# 01_V5_SYS.net
KiCad netlist of a schematic drawn in Altium Designer
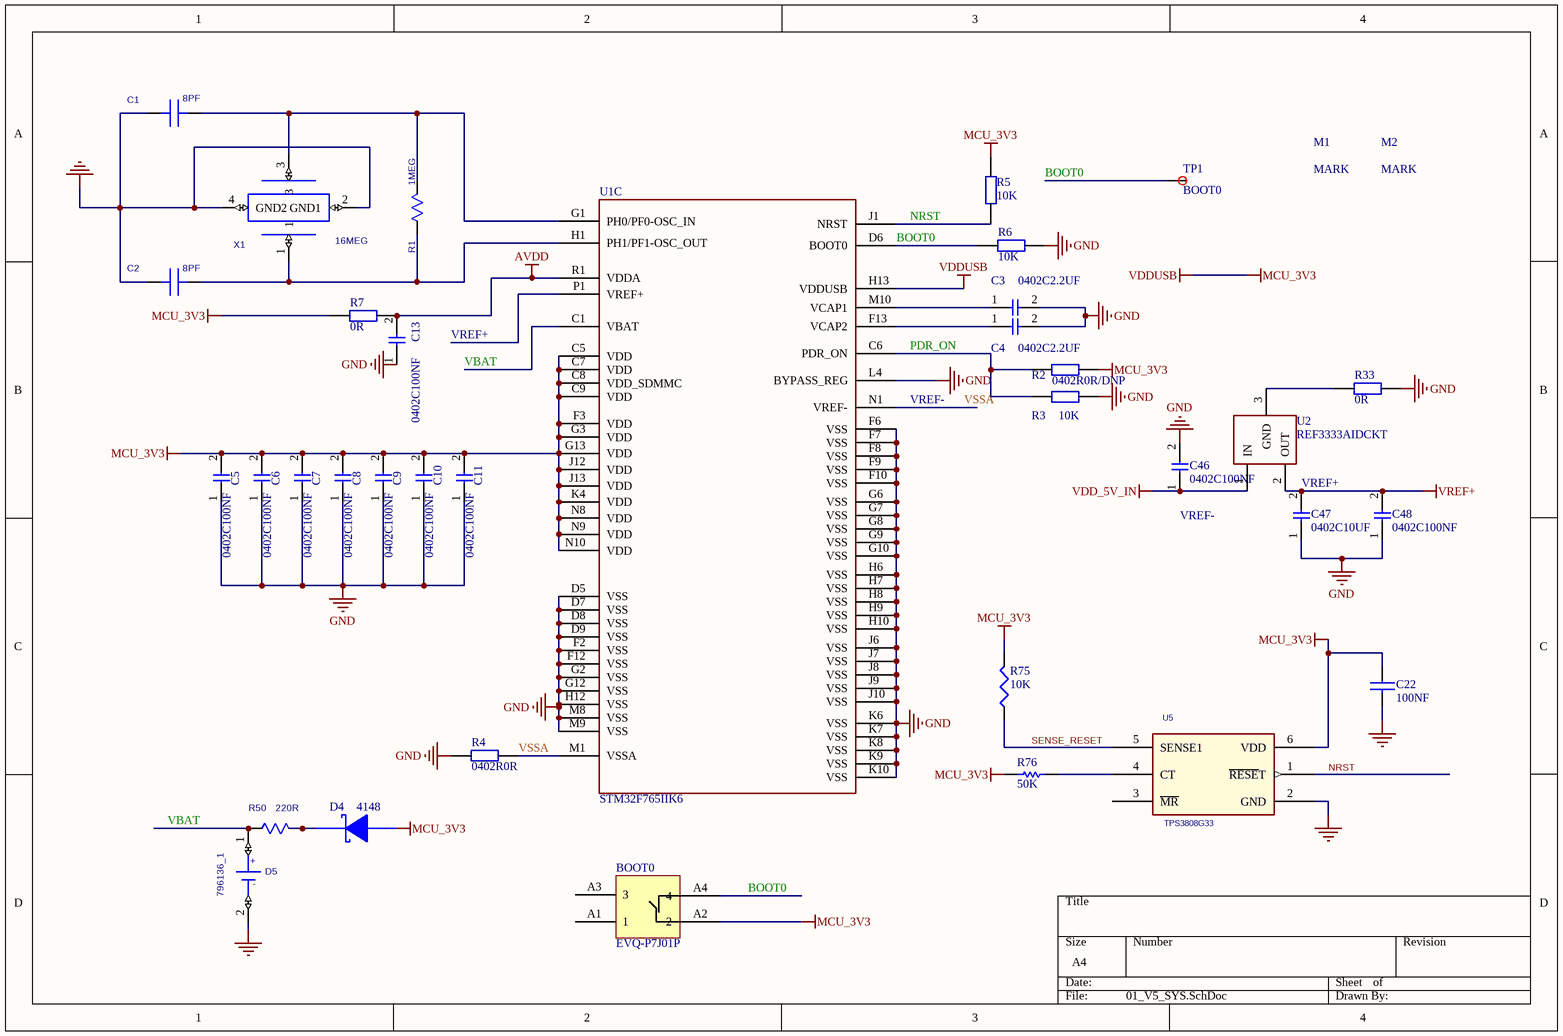
[diagram p0: 01_V5_SYS.SchDoc]

(export (version "E")
  (design (tool "Eeschema 10.0.6"))
  (components
    (comp (ref "BOOT0")
      (value "EVQ-P7J01P")
      (footprint "EVQ-P7J01P")
      (libsource (lib "hack") (part "EVQ-P7J01P"))
    )
    (comp (ref "C1") (value "8PF") (footprint "SC0402") (libsource (lib "*") (part "C")))
    (comp (ref "C2") (value "8PF") (footprint "SC0402") (libsource (lib "*") (part "C")))
    (comp (ref "C3") (value "0402C2.2UF") (footprint "0402C") (libsource (lib "CUAV") (part "0402C2.2UF")))
    (comp (ref "C4") (value "0402C2.2UF") (footprint "0402C") (libsource (lib "CUAV") (part "0402C2.2UF")))
    (comp (ref "C5")
      (value "0402C100NF")
      (footprint "0402C")
      (description "50V 5%")
      (libsource (lib "CUAV") (part "0402C100NF"))
    )
    (comp (ref "C6")
      (value "0402C100NF")
      (footprint "0402C")
      (description "50V 5%")
      (libsource (lib "CUAV") (part "0402C100NF"))
    )
    (comp (ref "C7")
      (value "0402C100NF")
      (footprint "0402C")
      (description "50V 5%")
      (libsource (lib "CUAV") (part "0402C100NF"))
    )
    (comp (ref "C8")
      (value "0402C100NF")
      (footprint "0402C")
      (description "50V 5%")
      (libsource (lib "CUAV") (part "0402C100NF"))
    )
    (comp (ref "C9")
      (value "0402C100NF")
      (footprint "0402C")
      (description "50V 5%")
      (libsource (lib "CUAV") (part "0402C100NF"))
    )
    (comp (ref "C10")
      (value "0402C100NF")
      (footprint "0402C")
      (description "50V 5%")
      (libsource (lib "CUAV") (part "0402C100NF"))
    )
    (comp (ref "C11")
      (value "0402C100NF")
      (footprint "0402C")
      (description "50V 5%")
      (libsource (lib "CUAV") (part "0402C100NF"))
    )
    (comp (ref "C13")
      (value "0402C100NF")
      (footprint "0402C")
      (description "50V 5%")
      (libsource (lib "CUAV") (part "0402C100NF"))
    )
    (comp (ref "C22")
      (value "100NF")
      (footprint "0402cap")
      (libsource (lib "Integrated_Library_RF_FEB_2012") (part "C1005X5R1H104K"))
    )
    (comp (ref "C46") (value "0402C100NF") (footprint "0402C") (libsource (lib "CUAV") (part "0402C2.2UF")))
    (comp (ref "C47") (value "0402C10UF") (footprint "0402C") (libsource (lib "CUAV") (part "0402C2.2UF")))
    (comp (ref "C48") (value "0402C100NF") (footprint "0402C") (libsource (lib "CUAV") (part "0402C2.2UF")))
    (comp (ref "D4")
      (value "4148")
      (footprint "SOD323")
      (description "STPS20M100SG-TR")
      (libsource (lib "TI WEBENCH") (part "D1"))
    )
    (comp (ref "D5")
      (value "PWR1-2")
      (footprint "PAS414R-S-VE5R")
      (fields (field (name "DEVICE") "796136_1"))
      (libsource (lib "*") (part "PWR1-2_1"))
    )
    (comp (ref "M1") (value "MARK") (footprint "MARK") (libsource (lib "CUAV") (part "MARK")))
    (comp (ref "M2") (value "MARK") (footprint "MARK") (libsource (lib "CUAV") (part "MARK")))
    (comp (ref "R1") (value "1MEG") (footprint "SR0402") (libsource (lib "*") (part "R")))
    (comp (ref "R2")
      (value "0402R0R/DNP")
      (footprint "0402R")
      (description "0402R0R 1%")
      (libsource (lib "CUAV") (part "0402R0R"))
    )
    (comp (ref "R3")
      (value "10K")
      (footprint "0402R")
      (description "0402R0R 1%")
      (libsource (lib "CUAV") (part "0402R0R"))
    )
    (comp (ref "R4")
      (value "0402R0R")
      (footprint "0402R")
      (description "0402R0R 1%")
      (libsource (lib "CUAV") (part "0402R0R"))
    )
    (comp (ref "R5")
      (value "10K")
      (footprint "0402R")
      (description "0402R0R 1%")
      (libsource (lib "") (part "0402R0R_1"))
    )
    (comp (ref "R6")
      (value "10K")
      (footprint "0402R")
      (description "0402R0R 1%")
      (libsource (lib "") (part "0402R0R_2"))
    )
    (comp (ref "R7")
      (value "0R")
      (footprint "0402R")
      (description "0402R0R 1%")
      (libsource (lib "") (part "0402R0R_2"))
    )
    (comp (ref "R33")
      (value "0R")
      (footprint "0402R")
      (description "0402R0R 1%")
      (libsource (lib "") (part "0402R0R_2"))
    )
    (comp (ref "R50") (value "220R") (footprint "0402r") (libsource (lib "*") (part "R")))
    (comp (ref "R75")
      (value "10K")
      (footprint "R0402")
      (libsource (lib "Integrated_Library_RF_FEB_2012") (part "RMCF0402FT4K99"))
    )
    (comp (ref "R76")
      (value "50K")
      (footprint "0402R")
      (description "Semiconductor Resistor")
      (libsource (lib "Miscellaneous Devices") (part "Res Semi"))
    )
    (comp (ref "TP1")
      (value "BOOT0")
      (footprint "TP0.75")
      (description "TP_0.75MM")
      (libsource (lib "CUAV") (part "TP_0.75"))
    )
    (comp (ref "U1")
      (value "STM32F765IIK6")
      (footprint "UFBGA176")
      (libsource (lib "CUAV") (part "STM32F765IIK6"))
    )
    (comp (ref "U2")
      (value "REF3333AIDCKT")
      (footprint "SC70")
      (libsource (lib "CUAV") (part "REF3333AIDCKT"))
    )
    (comp (ref "U5")
      (value "TPS3808G33")
      (footprint "SOT-23-6")
      (description "IC VOLT SUPERVISOR 0.9V SOT23-6")
      (fields (field (name "PART #") "102020-0009R") (field (name "MANUFACTURER") "Texas Instruments"))
      (libsource (lib "Integrated_Library_RF_FEB_2012") (part "TPS3808G09DBVR"))
    )
    (comp (ref "X1") (value "16MEG") (footprint "3225") (libsource (lib "*") (part "X_B")))
  )
  (nets
    (net (code "1") (name "/BOOT0") (class "Default")
      (node (ref "BOOT0") (pin "A4") (pinfunction "4_A4") (pintype "passive"))
      (node (ref "R6") (pin "2") (pintype "passive"))
      (node (ref "TP1") (pin "0") (pintype "passive"))
      (node (ref "U1") (pin "D6") (pinfunction "BOOT0_D6") (pintype "passive"))
    )
    (net (code "2") (name "/NRST") (class "Default")
      (node (ref "R5") (pin "1") (pintype "passive"))
      (node (ref "U1") (pin "J1") (pinfunction "NRST_J1") (pintype "passive"))
      (node (ref "U5") (pin "1") (pinfunction "~{RESE}T_1") (pintype "output"))
    )
    (net (code "3") (name "/PDR_ON") (class "Default")
      (node (ref "R2") (pin "1") (pintype "passive"))
      (node (ref "R3") (pin "1") (pintype "passive"))
      (node (ref "U1") (pin "C6") (pinfunction "PDR_ON_C6") (pintype "passive"))
    )
    (net (code "4") (name "/SENSE_RESET") (class "Default")
      (node (ref "R75") (pin "1") (pinfunction "1_1") (pintype "passive"))
      (node (ref "U5") (pin "5") (pinfunction "SENSE1_5") (pintype "passive"))
    )
    (net (code "5") (name "/VBAT") (class "Default")
      (node (ref "D5") (pin "1") (pinfunction "+_1") (pintype "bidirectional"))
      (node (ref "R50") (pin "1") (pinfunction "A_1") (pintype "bidirectional"))
      (node (ref "U1") (pin "C1") (pinfunction "VBAT_C1") (pintype "passive"))
    )
    (net (code "6") (name "/VREF-") (class "Default")
      (node (ref "R4") (pin "2") (pintype "passive"))
      (node (ref "U1") (pin "M1") (pinfunction "VSSA_M1") (pintype "passive"))
      (node (ref "U1") (pin "N1") (pinfunction "VREF-_N1") (pintype "passive"))
    )
    (net (code "7") (name "AVDD") (class "Default")
      (node (ref "C13") (pin "2") (pintype "passive"))
      (node (ref "R7") (pin "1") (pintype "passive"))
      (node (ref "U1") (pin "R1") (pinfunction "VDDA_R1") (pintype "passive"))
    )
    (net (code "8") (name "GND") (class "Default")
      (node (ref "C1") (pin "1") (pinfunction "A_1") (pintype "bidirectional"))
      (node (ref "C10") (pin "1") (pintype "passive"))
      (node (ref "C11") (pin "1") (pintype "passive"))
      (node (ref "C13") (pin "1") (pintype "passive"))
      (node (ref "C2") (pin "1") (pinfunction "A_1") (pintype "bidirectional"))
      (node (ref "C22") (pin "2") (pinfunction "2_2") (pintype "passive"))
      (node (ref "C3") (pin "2") (pintype "passive"))
      (node (ref "C4") (pin "2") (pintype "passive"))
      (node (ref "C46") (pin "2") (pintype "passive"))
      (node (ref "C47") (pin "1") (pintype "passive"))
      (node (ref "C48") (pin "1") (pintype "passive"))
      (node (ref "C5") (pin "1") (pintype "passive"))
      (node (ref "C6") (pin "1") (pintype "passive"))
      (node (ref "C7") (pin "1") (pintype "passive"))
      (node (ref "C8") (pin "1") (pintype "passive"))
      (node (ref "C9") (pin "1") (pintype "passive"))
      (node (ref "D5") (pin "2") (pinfunction "-_2") (pintype "bidirectional"))
      (node (ref "R3") (pin "2") (pintype "passive"))
      (node (ref "R33") (pin "1") (pintype "passive"))
      (node (ref "R4") (pin "1") (pintype "passive"))
      (node (ref "R6") (pin "1") (pintype "passive"))
      (node (ref "U1") (pin "D5") (pinfunction "VSS_D5") (pintype "passive"))
      (node (ref "U1") (pin "D7") (pinfunction "VSS_D7") (pintype "passive"))
      (node (ref "U1") (pin "D8") (pinfunction "VSS_D8") (pintype "passive"))
      (node (ref "U1") (pin "D9") (pinfunction "VSS_D9") (pintype "passive"))
      (node (ref "U1") (pin "F10") (pinfunction "VSS_F10") (pintype "passive"))
      (node (ref "U1") (pin "F12") (pinfunction "VSS_F12") (pintype "passive"))
      (node (ref "U1") (pin "F2") (pinfunction "VSS_F2") (pintype "passive"))
      (node (ref "U1") (pin "F6") (pinfunction "VSS_F6") (pintype "passive"))
      (node (ref "U1") (pin "F7") (pinfunction "VSS_F7") (pintype "passive"))
      (node (ref "U1") (pin "F8") (pinfunction "VSS_F8") (pintype "passive"))
      (node (ref "U1") (pin "F9") (pinfunction "VSS_F9") (pintype "passive"))
      (node (ref "U1") (pin "G10") (pinfunction "VSS_G10") (pintype "passive"))
      (node (ref "U1") (pin "G12") (pinfunction "VSS_G12") (pintype "passive"))
      (node (ref "U1") (pin "G2") (pinfunction "VSS_G2") (pintype "passive"))
      (node (ref "U1") (pin "G6") (pinfunction "VSS_G6") (pintype "passive"))
      (node (ref "U1") (pin "G7") (pinfunction "VSS_G7") (pintype "passive"))
      (node (ref "U1") (pin "G8") (pinfunction "VSS_G8") (pintype "passive"))
      (node (ref "U1") (pin "G9") (pinfunction "VSS_G9") (pintype "passive"))
      (node (ref "U1") (pin "H10") (pinfunction "VSS_H10") (pintype "passive"))
      (node (ref "U1") (pin "H12") (pinfunction "VSS_H12") (pintype "passive"))
      (node (ref "U1") (pin "H6") (pinfunction "VSS_H6") (pintype "passive"))
      (node (ref "U1") (pin "H7") (pinfunction "VSS_H7") (pintype "passive"))
      (node (ref "U1") (pin "H8") (pinfunction "VSS_H8") (pintype "passive"))
      (node (ref "U1") (pin "H9") (pinfunction "VSS_H9") (pintype "passive"))
      (node (ref "U1") (pin "J10") (pinfunction "VSS_J10") (pintype "passive"))
      (node (ref "U1") (pin "J6") (pinfunction "VSS_J6") (pintype "passive"))
      (node (ref "U1") (pin "J7") (pinfunction "VSS_J7") (pintype "passive"))
      (node (ref "U1") (pin "J8") (pinfunction "VSS_J8") (pintype "passive"))
      (node (ref "U1") (pin "J9") (pinfunction "VSS_J9") (pintype "passive"))
      (node (ref "U1") (pin "K10") (pinfunction "VSS_K10") (pintype "passive"))
      (node (ref "U1") (pin "K6") (pinfunction "VSS_K6") (pintype "passive"))
      (node (ref "U1") (pin "K7") (pinfunction "VSS_K7") (pintype "passive"))
      (node (ref "U1") (pin "K8") (pinfunction "VSS_K8") (pintype "passive"))
      (node (ref "U1") (pin "K9") (pinfunction "VSS_K9") (pintype "passive"))
      (node (ref "U1") (pin "L4") (pinfunction "BYPASS_REG_L4") (pintype "passive"))
      (node (ref "U1") (pin "M8") (pinfunction "VSS_M8") (pintype "passive"))
      (node (ref "U1") (pin "M9") (pinfunction "VSS_M9") (pintype "passive"))
      (node (ref "U5") (pin "2") (pinfunction "GND_2") (pintype "passive"))
      (node (ref "X1") (pin "2") (pinfunction "GND1_2") (pintype "bidirectional"))
      (node (ref "X1") (pin "4") (pinfunction "GND2_4") (pintype "bidirectional"))
    )
    (net (code "9") (name "MCU_3V3") (class "Default")
      (node (ref "BOOT0") (pin "A2") (pinfunction "2_A2") (pintype "passive"))
      (node (ref "C10") (pin "2") (pintype "passive"))
      (node (ref "C11") (pin "2") (pintype "passive"))
      (node (ref "C22") (pin "1") (pinfunction "1_1") (pintype "passive"))
      (node (ref "C5") (pin "2") (pintype "passive"))
      (node (ref "C6") (pin "2") (pintype "passive"))
      (node (ref "C7") (pin "2") (pintype "passive"))
      (node (ref "C8") (pin "2") (pintype "passive"))
      (node (ref "C9") (pin "2") (pintype "passive"))
      (node (ref "D4") (pin "A") (pinfunction "A_A") (pintype "passive"))
      (node (ref "R2") (pin "2") (pintype "passive"))
      (node (ref "R5") (pin "2") (pintype "passive"))
      (node (ref "R7") (pin "2") (pintype "passive"))
      (node (ref "R75") (pin "2") (pinfunction "2_2") (pintype "passive"))
      (node (ref "R76") (pin "2") (pinfunction "2_2") (pintype "passive"))
      (node (ref "U1") (pin "C5") (pinfunction "VDD_C5") (pintype "passive"))
      (node (ref "U1") (pin "C7") (pinfunction "VDD_C7") (pintype "passive"))
      (node (ref "U1") (pin "C8") (pinfunction "VDD_SDMMC_C8") (pintype "passive"))
      (node (ref "U1") (pin "C9") (pinfunction "VDD_C9") (pintype "passive"))
      (node (ref "U1") (pin "F3") (pinfunction "VDD_F3") (pintype "passive"))
      (node (ref "U1") (pin "G13") (pinfunction "VDD_G13") (pintype "passive"))
      (node (ref "U1") (pin "G3") (pinfunction "VDD_G3") (pintype "passive"))
      (node (ref "U1") (pin "H13") (pinfunction "VDDUSB_H13") (pintype "passive"))
      (node (ref "U1") (pin "J12") (pinfunction "VDD_J12") (pintype "passive"))
      (node (ref "U1") (pin "J13") (pinfunction "VDD_J13") (pintype "passive"))
      (node (ref "U1") (pin "K4") (pinfunction "VDD_K4") (pintype "passive"))
      (node (ref "U1") (pin "N10") (pinfunction "VDD_N10") (pintype "passive"))
      (node (ref "U1") (pin "N8") (pinfunction "VDD_N8") (pintype "passive"))
      (node (ref "U1") (pin "N9") (pinfunction "VDD_N9") (pintype "passive"))
      (node (ref "U5") (pin "6") (pinfunction "VDD_6") (pintype "passive"))
    )
    (net (code "10") (name "Net-(C1-B)") (class "Default")
      (node (ref "C1") (pin "2") (pinfunction "B_2") (pintype "bidirectional"))
      (node (ref "R1") (pin "2") (pinfunction "B_2") (pintype "bidirectional"))
      (node (ref "U1") (pin "G1") (pinfunction "PH0/PF0-OSC_IN_G1") (pintype "passive"))
      (node (ref "X1") (pin "3") (pinfunction "3_3") (pintype "bidirectional"))
    )
    (net (code "11") (name "Net-(C2-B)") (class "Default")
      (node (ref "C2") (pin "2") (pinfunction "B_2") (pintype "bidirectional"))
      (node (ref "R1") (pin "1") (pinfunction "A_1") (pintype "bidirectional"))
      (node (ref "U1") (pin "H1") (pinfunction "PH1/PF1-OSC_OUT_H1") (pintype "passive"))
      (node (ref "X1") (pin "1") (pinfunction "1_1") (pintype "bidirectional"))
    )
    (net (code "12") (name "Net-(R50-B)") (class "Default")
      (node (ref "D4") (pin "K") (pinfunction "K_K") (pintype "passive"))
      (node (ref "R50") (pin "2") (pinfunction "B_2") (pintype "bidirectional"))
    )
    (net (code "13") (name "Net-(U1C-VCAP1)") (class "Default")
      (node (ref "C3") (pin "1") (pintype "passive"))
      (node (ref "U1") (pin "M10") (pinfunction "VCAP1_M10") (pintype "passive"))
    )
    (net (code "14") (name "Net-(U1C-VCAP2)") (class "Default")
      (node (ref "C4") (pin "1") (pintype "passive"))
      (node (ref "U1") (pin "F13") (pinfunction "VCAP2_F13") (pintype "passive"))
    )
    (net (code "15") (name "Net-(U2-GND)") (class "Default")
      (node (ref "R33") (pin "2") (pintype "passive"))
      (node (ref "U2") (pin "3") (pinfunction "GND_3") (pintype "passive"))
    )
    (net (code "16") (name "Net-(U5-CT)") (class "Default")
      (node (ref "R76") (pin "1") (pinfunction "1_1") (pintype "passive"))
      (node (ref "U5") (pin "4") (pinfunction "CT_4") (pintype "passive"))
    )
    (net (code "17") (name "VDD_5V_IN") (class "Default")
      (node (ref "C46") (pin "1") (pintype "passive"))
      (node (ref "U2") (pin "1") (pinfunction "IN_1") (pintype "passive"))
    )
    (net (code "18") (name "VREF+") (class "Default")
      (node (ref "C47") (pin "2") (pintype "passive"))
      (node (ref "C48") (pin "2") (pintype "passive"))
      (node (ref "U1") (pin "P1") (pinfunction "VREF+_P1") (pintype "passive"))
      (node (ref "U2") (pin "2") (pinfunction "OUT_2") (pintype "passive"))
    )
    (net (code "19") (name "unconnected-(BOOT0-1-PadA1)") (class "Default")
      (node (ref "BOOT0") (pin "A1") (pinfunction "1_A1") (pintype "passive"))
    )
    (net (code "20") (name "unconnected-(BOOT0-3-PadA3)") (class "Default")
      (node (ref "BOOT0") (pin "A3") (pinfunction "3_A3") (pintype "passive"))
    )
    (net (code "21") (name "unconnected-(U5-~{MR}-Pad3)") (class "Default")
      (node (ref "U5") (pin "3") (pinfunction "~{MR}_3") (pintype "passive"))
    )
  )
)
